# Felderblock6-a-2.net
KiCad netlist of a schematic drawn in EAGLE
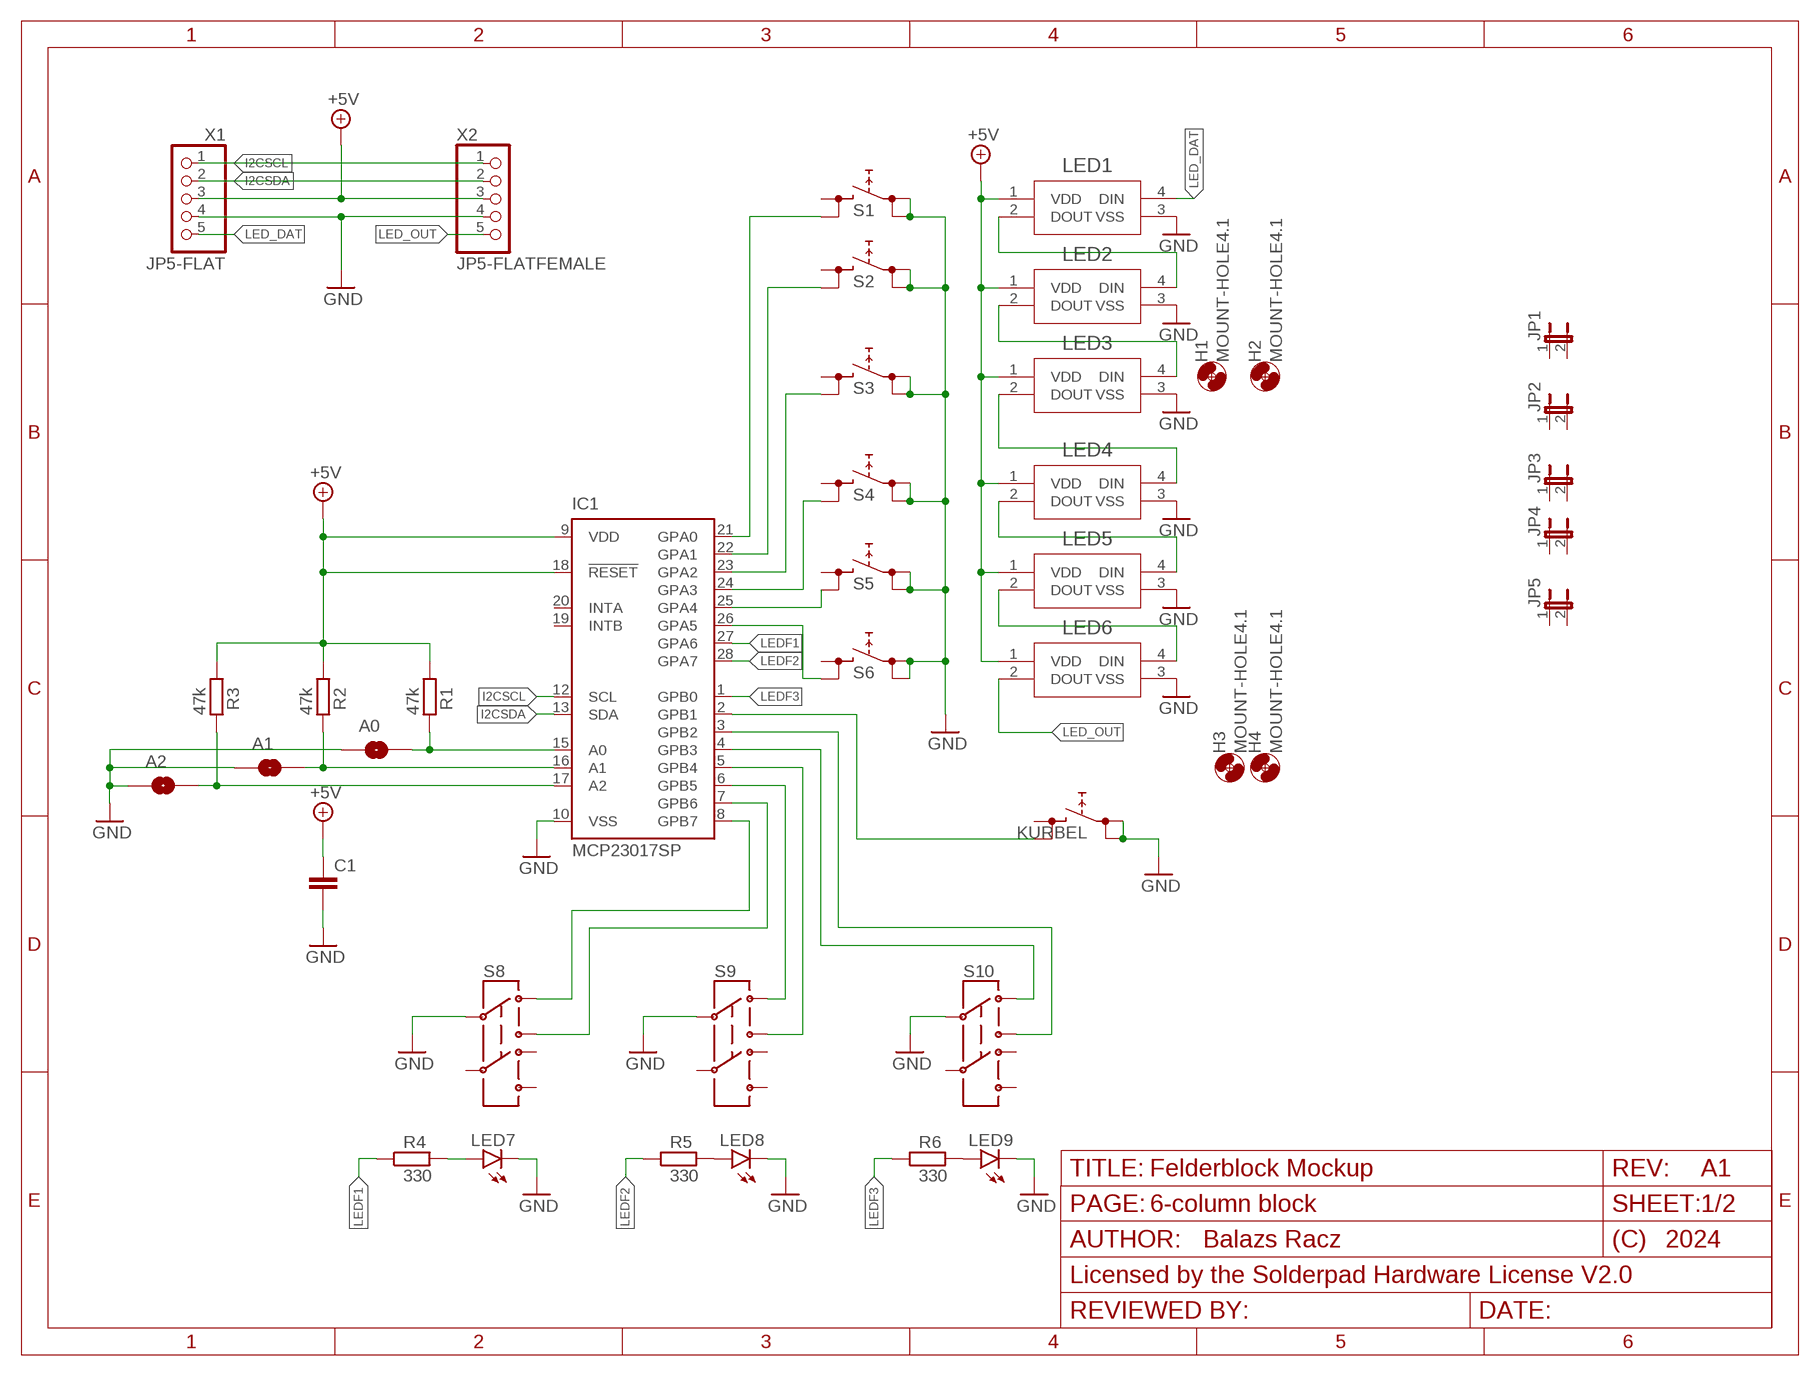
[diagram p0: schematic, sheet 1]

(export (version "E")
  (design (tool "Eeschema 10.0.6"))
  (components
    (comp (ref "A0")
      (value "SJRND2")
      (footprint "eagle-import:SJ_RND2")
      (libsource (lib "eagle-import") (part "SJRND2"))
    )
    (comp (ref "A1")
      (value "SJRND2")
      (footprint "eagle-import:SJ_RND2")
      (libsource (lib "eagle-import") (part "SJRND2"))
    )
    (comp (ref "A2")
      (value "SJRND2")
      (footprint "eagle-import:SJ_RND2")
      (libsource (lib "eagle-import") (part "SJRND2"))
    )
    (comp (ref "C1")
      (value "C-EUC0805")
      (footprint "eagle-import:C0805")
      (libsource (lib "eagle-import") (part "C-EUC0805"))
    )
    (comp (ref "H1")
      (value "MOUNT-HOLE4.1")
      (footprint "eagle-import:4,1")
      (libsource (lib "eagle-import") (part "MOUNT-HOLE4.1"))
    )
    (comp (ref "H2")
      (value "MOUNT-HOLE4.1")
      (footprint "eagle-import:4,1")
      (libsource (lib "eagle-import") (part "MOUNT-HOLE4.1"))
    )
    (comp (ref "H3")
      (value "MOUNT-HOLE4.1")
      (footprint "eagle-import:4,1")
      (libsource (lib "eagle-import") (part "MOUNT-HOLE4.1"))
    )
    (comp (ref "H4")
      (value "MOUNT-HOLE4.1")
      (footprint "eagle-import:4,1")
      (libsource (lib "eagle-import") (part "MOUNT-HOLE4.1"))
    )
    (comp (ref "IC1")
      (value "MCP23017SP")
      (footprint "eagle-import:DIL28-3")
      (fields (field (name "MF") "MICROCHIP") (field (name "MPN") "MCP23017-E/SP"))
      (libsource (lib "eagle-import") (part "MCP23017SP"))
    )
    (comp (ref "JP1")
      (value "FELD-BOARD-HOLDER")
      (footprint "eagle-import:FELD-BOARD-HOLDER")
      (libsource (lib "eagle-import") (part "FELD-BOARD-HOLDER"))
    )
    (comp (ref "JP2")
      (value "FELD-BOARD-HOLDER")
      (footprint "eagle-import:FELD-BOARD-HOLDER")
      (libsource (lib "eagle-import") (part "FELD-BOARD-HOLDER"))
    )
    (comp (ref "JP3")
      (value "FELD-BOARD-HOLDER")
      (footprint "eagle-import:FELD-BOARD-HOLDER")
      (libsource (lib "eagle-import") (part "FELD-BOARD-HOLDER"))
    )
    (comp (ref "JP4")
      (value "FELD-BOARD-HOLDER")
      (footprint "eagle-import:FELD-BOARD-HOLDER")
      (libsource (lib "eagle-import") (part "FELD-BOARD-HOLDER"))
    )
    (comp (ref "JP5")
      (value "FELD-BOARD-HOLDER")
      (footprint "eagle-import:FELD-BOARD-HOLDER")
      (libsource (lib "eagle-import") (part "FELD-BOARD-HOLDER"))
    )
    (comp (ref "KURBEL")
      (value "W1")
      (footprint "eagle-import:TACTSW-6X6")
      (libsource (lib "eagle-import") (part "TACTSW-6X6S"))
    )
    (comp (ref "LED1")
      (value "LED-2812BCOM-16347_SPK-M")
      (footprint "eagle-import:COM-16347_SPK-M")
      (fields
        (field (name "MANUFACTURER_PART_NUMBER") "COM-16347")
        (field (name "COPYRIGHT") "Copyright (C) 2024 Ultra Librarian. All rights reserved.")
      )
      (libsource (lib "eagle-import") (part "LED-2812BCOM-16347_SPK-M"))
    )
    (comp (ref "LED2")
      (value "LED-2812BCOM-16347_SPK-M")
      (footprint "eagle-import:COM-16347_SPK-M")
      (fields
        (field (name "MANUFACTURER_PART_NUMBER") "COM-16347")
        (field (name "COPYRIGHT") "Copyright (C) 2024 Ultra Librarian. All rights reserved.")
      )
      (libsource (lib "eagle-import") (part "LED-2812BCOM-16347_SPK-M"))
    )
    (comp (ref "LED3")
      (value "LED-2812BCOM-16347_SPK-M")
      (footprint "eagle-import:COM-16347_SPK-M")
      (fields
        (field (name "MANUFACTURER_PART_NUMBER") "COM-16347")
        (field (name "COPYRIGHT") "Copyright (C) 2024 Ultra Librarian. All rights reserved.")
      )
      (libsource (lib "eagle-import") (part "LED-2812BCOM-16347_SPK-M"))
    )
    (comp (ref "LED4")
      (value "LED-2812BCOM-16347_SPK-M")
      (footprint "eagle-import:COM-16347_SPK-M")
      (fields
        (field (name "MANUFACTURER_PART_NUMBER") "COM-16347")
        (field (name "COPYRIGHT") "Copyright (C) 2024 Ultra Librarian. All rights reserved.")
      )
      (libsource (lib "eagle-import") (part "LED-2812BCOM-16347_SPK-M"))
    )
    (comp (ref "LED5")
      (value "LED-2812BCOM-16347_SPK-M")
      (footprint "eagle-import:COM-16347_SPK-M")
      (fields
        (field (name "MANUFACTURER_PART_NUMBER") "COM-16347")
        (field (name "COPYRIGHT") "Copyright (C) 2024 Ultra Librarian. All rights reserved.")
      )
      (libsource (lib "eagle-import") (part "LED-2812BCOM-16347_SPK-M"))
    )
    (comp (ref "LED6")
      (value "LED-2812BCOM-16347_SPK-M")
      (footprint "eagle-import:COM-16347_SPK-M")
      (fields
        (field (name "MANUFACTURER_PART_NUMBER") "COM-16347")
        (field (name "COPYRIGHT") "Copyright (C) 2024 Ultra Librarian. All rights reserved.")
      )
      (libsource (lib "eagle-import") (part "LED-2812BCOM-16347_SPK-M"))
    )
    (comp (ref "LED7")
      (value "LEDCHIPLED_0805")
      (footprint "eagle-import:CHIPLED_0805")
      (libsource (lib "eagle-import") (part "LEDCHIPLED_0805"))
    )
    (comp (ref "LED8")
      (value "LEDCHIPLED_0805")
      (footprint "eagle-import:CHIPLED_0805")
      (libsource (lib "eagle-import") (part "LEDCHIPLED_0805"))
    )
    (comp (ref "LED9")
      (value "LEDCHIPLED_0805")
      (footprint "eagle-import:CHIPLED_0805")
      (libsource (lib "eagle-import") (part "LEDCHIPLED_0805"))
    )
    (comp (ref "R1")
      (value "47k")
      (footprint "eagle-import:R0805")
      (libsource (lib "eagle-import") (part "R-EU_R0805"))
    )
    (comp (ref "R2")
      (value "47k")
      (footprint "eagle-import:R0805")
      (libsource (lib "eagle-import") (part "R-EU_R0805"))
    )
    (comp (ref "R3")
      (value "47k")
      (footprint "eagle-import:R0805")
      (libsource (lib "eagle-import") (part "R-EU_R0805"))
    )
    (comp (ref "R4")
      (value "330")
      (footprint "eagle-import:R0805")
      (libsource (lib "eagle-import") (part "R-EU_R0805"))
    )
    (comp (ref "R5")
      (value "330")
      (footprint "eagle-import:R0805")
      (libsource (lib "eagle-import") (part "R-EU_R0805"))
    )
    (comp (ref "R6")
      (value "330")
      (footprint "eagle-import:R0805")
      (libsource (lib "eagle-import") (part "R-EU_R0805"))
    )
    (comp (ref "S1")
      (value "W1")
      (footprint "eagle-import:TACTSW-6X6")
      (libsource (lib "eagle-import") (part "TACTSW-6X6S"))
    )
    (comp (ref "S2")
      (value "W1")
      (footprint "eagle-import:TACTSW-6X6")
      (libsource (lib "eagle-import") (part "TACTSW-6X6S"))
    )
    (comp (ref "S3")
      (value "W1")
      (footprint "eagle-import:TACTSW-6X6")
      (libsource (lib "eagle-import") (part "TACTSW-6X6S"))
    )
    (comp (ref "S4")
      (value "W1")
      (footprint "eagle-import:TACTSW-6X6")
      (libsource (lib "eagle-import") (part "TACTSW-6X6S"))
    )
    (comp (ref "S5")
      (value "W1")
      (footprint "eagle-import:TACTSW-6X6")
      (libsource (lib "eagle-import") (part "TACTSW-6X6S"))
    )
    (comp (ref "S6")
      (value "W1")
      (footprint "eagle-import:TACTSW-6X6")
      (libsource (lib "eagle-import") (part "TACTSW-6X6S"))
    )
    (comp (ref "S8")
      (value "SWITCH-DPDT")
      (footprint "eagle-import:DP-T1")
      (libsource (lib "eagle-import") (part "SWITCH-DPDT"))
    )
    (comp (ref "S9")
      (value "SWITCH-DPDT")
      (footprint "eagle-import:DP-T1")
      (libsource (lib "eagle-import") (part "SWITCH-DPDT"))
    )
    (comp (ref "S10")
      (value "SWITCH-DPDT")
      (footprint "eagle-import:DP-T1")
      (libsource (lib "eagle-import") (part "SWITCH-DPDT"))
    )
    (comp (ref "X1")
      (value "JP5-FLAT")
      (footprint "eagle-import:JP5F")
      (libsource (lib "eagle-import") (part "JP5-FLAT"))
    )
    (comp (ref "X2")
      (value "JP5-FLATFEMALE")
      (footprint "eagle-import:JP5F-FEM")
      (libsource (lib "eagle-import") (part "JP5-FLATFEMALE"))
    )
  )
  (nets
    (net (code "1") (name "+5V") (class "Default")
      (node (ref "C1") (pin "1") (pinfunction "1_1") (pintype "passive"))
      (node (ref "IC1") (pin "18") (pinfunction "~{RESET}_18") (pintype "input"))
      (node (ref "IC1") (pin "9") (pinfunction "VDD_9") (pintype "power_in"))
      (node (ref "LED1") (pin "1") (pinfunction "VDD_1") (pintype "power_in"))
      (node (ref "LED2") (pin "1") (pinfunction "VDD_1") (pintype "power_in"))
      (node (ref "LED3") (pin "1") (pinfunction "VDD_1") (pintype "power_in"))
      (node (ref "LED4") (pin "1") (pinfunction "VDD_1") (pintype "power_in"))
      (node (ref "LED5") (pin "1") (pinfunction "VDD_1") (pintype "power_in"))
      (node (ref "LED6") (pin "1") (pinfunction "VDD_1") (pintype "power_in"))
      (node (ref "R1") (pin "1") (pinfunction "1_1") (pintype "passive"))
      (node (ref "R2") (pin "1") (pinfunction "1_1") (pintype "passive"))
      (node (ref "R3") (pin "1") (pinfunction "1_1") (pintype "passive"))
      (node (ref "X1") (pin "3") (pinfunction "3_3") (pintype "passive"))
      (node (ref "X2") (pin "3") (pinfunction "3_3") (pintype "passive"))
    )
    (net (code "2") (name "GND") (class "Default")
      (node (ref "A0") (pin "P$1") (pinfunction "1_P$1") (pintype "passive"))
      (node (ref "A1") (pin "P$1") (pinfunction "1_P$1") (pintype "passive"))
      (node (ref "A2") (pin "P$1") (pinfunction "1_P$1") (pintype "passive"))
      (node (ref "C1") (pin "2") (pinfunction "2_2") (pintype "passive"))
      (node (ref "IC1") (pin "10") (pinfunction "VSS_10") (pintype "power_in"))
      (node (ref "KURBEL") (pin "1") (pinfunction "1.1_1") (pintype "passive"))
      (node (ref "KURBEL") (pin "2") (pinfunction "1.2_2") (pintype "passive"))
      (node (ref "LED1") (pin "3") (pinfunction "VSS_3") (pintype "passive"))
      (node (ref "LED2") (pin "3") (pinfunction "VSS_3") (pintype "passive"))
      (node (ref "LED3") (pin "3") (pinfunction "VSS_3") (pintype "passive"))
      (node (ref "LED4") (pin "3") (pinfunction "VSS_3") (pintype "passive"))
      (node (ref "LED5") (pin "3") (pinfunction "VSS_3") (pintype "passive"))
      (node (ref "LED6") (pin "3") (pinfunction "VSS_3") (pintype "passive"))
      (node (ref "LED7") (pin "C") (pinfunction "C_C") (pintype "passive"))
      (node (ref "LED8") (pin "C") (pinfunction "C_C") (pintype "passive"))
      (node (ref "LED9") (pin "C") (pinfunction "C_C") (pintype "passive"))
      (node (ref "S1") (pin "1") (pinfunction "1.1_1") (pintype "passive"))
      (node (ref "S1") (pin "2") (pinfunction "1.2_2") (pintype "passive"))
      (node (ref "S10") (pin "2") (pinfunction "1C_2") (pintype "bidirectional"))
      (node (ref "S2") (pin "1") (pinfunction "1.1_1") (pintype "passive"))
      (node (ref "S2") (pin "2") (pinfunction "1.2_2") (pintype "passive"))
      (node (ref "S3") (pin "1") (pinfunction "1.1_1") (pintype "passive"))
      (node (ref "S3") (pin "2") (pinfunction "1.2_2") (pintype "passive"))
      (node (ref "S4") (pin "1") (pinfunction "1.1_1") (pintype "passive"))
      (node (ref "S4") (pin "2") (pinfunction "1.2_2") (pintype "passive"))
      (node (ref "S5") (pin "1") (pinfunction "1.1_1") (pintype "passive"))
      (node (ref "S5") (pin "2") (pinfunction "1.2_2") (pintype "passive"))
      (node (ref "S6") (pin "1") (pinfunction "1.1_1") (pintype "passive"))
      (node (ref "S6") (pin "2") (pinfunction "1.2_2") (pintype "passive"))
      (node (ref "S8") (pin "2") (pinfunction "1C_2") (pintype "bidirectional"))
      (node (ref "S9") (pin "2") (pinfunction "1C_2") (pintype "bidirectional"))
      (node (ref "X1") (pin "4") (pinfunction "4_4") (pintype "passive"))
      (node (ref "X2") (pin "4") (pinfunction "4_4") (pintype "passive"))
    )
    (net (code "3") (name "I2CSCL") (class "Default")
      (node (ref "IC1") (pin "12") (pinfunction "SCL_12") (pintype "input"))
      (node (ref "X1") (pin "1") (pinfunction "1_1") (pintype "passive"))
      (node (ref "X2") (pin "1") (pinfunction "1_1") (pintype "passive"))
    )
    (net (code "4") (name "I2CSDA") (class "Default")
      (node (ref "IC1") (pin "13") (pinfunction "SDA_13") (pintype "bidirectional"))
      (node (ref "X1") (pin "2") (pinfunction "2_2") (pintype "passive"))
      (node (ref "X2") (pin "2") (pinfunction "2_2") (pintype "passive"))
    )
    (net (code "5") (name "LEDF1") (class "Default")
      (node (ref "IC1") (pin "27") (pinfunction "GPA6_27") (pintype "bidirectional"))
      (node (ref "R4") (pin "1") (pinfunction "1_1") (pintype "passive"))
    )
    (net (code "6") (name "LEDF2") (class "Default")
      (node (ref "IC1") (pin "28") (pinfunction "GPA7_28") (pintype "bidirectional"))
      (node (ref "R5") (pin "1") (pinfunction "1_1") (pintype "passive"))
    )
    (net (code "7") (name "LEDF3") (class "Default")
      (node (ref "IC1") (pin "1") (pinfunction "GPB0_1") (pintype "bidirectional"))
      (node (ref "R6") (pin "1") (pinfunction "1_1") (pintype "passive"))
    )
    (net (code "8") (name "LED_DAT") (class "Default")
      (node (ref "LED1") (pin "4") (pinfunction "DIN_4") (pintype "input"))
      (node (ref "X1") (pin "5") (pinfunction "5_5") (pintype "passive"))
    )
    (net (code "9") (name "LED_OUT") (class "Default")
      (node (ref "LED6") (pin "2") (pinfunction "DOUT_2") (pintype "output"))
      (node (ref "X2") (pin "5") (pinfunction "5_5") (pintype "passive"))
    )
    (net (code "10") (name "Net-(A0-2)") (class "Default")
      (node (ref "A0") (pin "P$2") (pinfunction "2_P$2") (pintype "passive"))
      (node (ref "IC1") (pin "15") (pinfunction "A0_15") (pintype "input"))
      (node (ref "R1") (pin "2") (pinfunction "2_2") (pintype "passive"))
    )
    (net (code "11") (name "Net-(A1-2)") (class "Default")
      (node (ref "A1") (pin "P$2") (pinfunction "2_P$2") (pintype "passive"))
      (node (ref "IC1") (pin "16") (pinfunction "A1_16") (pintype "input"))
      (node (ref "R2") (pin "2") (pinfunction "2_2") (pintype "passive"))
    )
    (net (code "12") (name "Net-(A2-2)") (class "Default")
      (node (ref "A2") (pin "P$2") (pinfunction "2_P$2") (pintype "passive"))
      (node (ref "IC1") (pin "17") (pinfunction "A2_17") (pintype "input"))
      (node (ref "R3") (pin "2") (pinfunction "2_2") (pintype "passive"))
    )
    (net (code "13") (name "Net-(IC1-GPA0)") (class "Default")
      (node (ref "IC1") (pin "21") (pinfunction "GPA0_21") (pintype "bidirectional"))
      (node (ref "S1") (pin "4") (pinfunction "2.2_4") (pintype "passive"))
    )
    (net (code "14") (name "Net-(IC1-GPA1)") (class "Default")
      (node (ref "IC1") (pin "22") (pinfunction "GPA1_22") (pintype "bidirectional"))
      (node (ref "S2") (pin "4") (pinfunction "2.2_4") (pintype "passive"))
    )
    (net (code "15") (name "Net-(IC1-GPA2)") (class "Default")
      (node (ref "IC1") (pin "23") (pinfunction "GPA2_23") (pintype "bidirectional"))
      (node (ref "S3") (pin "4") (pinfunction "2.2_4") (pintype "passive"))
    )
    (net (code "16") (name "Net-(IC1-GPA3)") (class "Default")
      (node (ref "IC1") (pin "24") (pinfunction "GPA3_24") (pintype "bidirectional"))
      (node (ref "S4") (pin "4") (pinfunction "2.2_4") (pintype "passive"))
    )
    (net (code "17") (name "Net-(IC1-GPA4)") (class "Default")
      (node (ref "IC1") (pin "25") (pinfunction "GPA4_25") (pintype "bidirectional"))
      (node (ref "S5") (pin "4") (pinfunction "2.2_4") (pintype "passive"))
    )
    (net (code "18") (name "Net-(IC1-GPA5)") (class "Default")
      (node (ref "IC1") (pin "26") (pinfunction "GPA5_26") (pintype "bidirectional"))
      (node (ref "S6") (pin "4") (pinfunction "2.2_4") (pintype "passive"))
    )
    (net (code "19") (name "Net-(IC1-GPB1)") (class "Default")
      (node (ref "IC1") (pin "2") (pinfunction "GPB1_2") (pintype "bidirectional"))
      (node (ref "KURBEL") (pin "4") (pinfunction "2.2_4") (pintype "passive"))
    )
    (net (code "20") (name "Net-(IC1-GPB2)") (class "Default")
      (node (ref "IC1") (pin "3") (pinfunction "GPB2_3") (pintype "bidirectional"))
      (node (ref "S10") (pin "3") (pinfunction "1B_3") (pintype "bidirectional"))
    )
    (net (code "21") (name "Net-(IC1-GPB3)") (class "Default")
      (node (ref "IC1") (pin "4") (pinfunction "GPB3_4") (pintype "bidirectional"))
      (node (ref "S10") (pin "1") (pinfunction "1A_1") (pintype "bidirectional"))
    )
    (net (code "22") (name "Net-(IC1-GPB4)") (class "Default")
      (node (ref "IC1") (pin "5") (pinfunction "GPB4_5") (pintype "bidirectional"))
      (node (ref "S9") (pin "3") (pinfunction "1B_3") (pintype "bidirectional"))
    )
    (net (code "23") (name "Net-(IC1-GPB5)") (class "Default")
      (node (ref "IC1") (pin "6") (pinfunction "GPB5_6") (pintype "bidirectional"))
      (node (ref "S9") (pin "1") (pinfunction "1A_1") (pintype "bidirectional"))
    )
    (net (code "24") (name "Net-(IC1-GPB6)") (class "Default")
      (node (ref "IC1") (pin "7") (pinfunction "GPB6_7") (pintype "bidirectional"))
      (node (ref "S8") (pin "3") (pinfunction "1B_3") (pintype "bidirectional"))
    )
    (net (code "25") (name "Net-(IC1-GPB7)") (class "Default")
      (node (ref "IC1") (pin "8") (pinfunction "GPB7_8") (pintype "bidirectional"))
      (node (ref "S8") (pin "1") (pinfunction "1A_1") (pintype "bidirectional"))
    )
    (net (code "26") (name "Net-(LED1-DOUT)") (class "Default")
      (node (ref "LED1") (pin "2") (pinfunction "DOUT_2") (pintype "output"))
      (node (ref "LED2") (pin "4") (pinfunction "DIN_4") (pintype "input"))
    )
    (net (code "27") (name "Net-(LED2-DOUT)") (class "Default")
      (node (ref "LED2") (pin "2") (pinfunction "DOUT_2") (pintype "output"))
      (node (ref "LED3") (pin "4") (pinfunction "DIN_4") (pintype "input"))
    )
    (net (code "28") (name "Net-(LED3-DOUT)") (class "Default")
      (node (ref "LED3") (pin "2") (pinfunction "DOUT_2") (pintype "output"))
      (node (ref "LED4") (pin "4") (pinfunction "DIN_4") (pintype "input"))
    )
    (net (code "29") (name "Net-(LED4-DOUT)") (class "Default")
      (node (ref "LED4") (pin "2") (pinfunction "DOUT_2") (pintype "output"))
      (node (ref "LED5") (pin "4") (pinfunction "DIN_4") (pintype "input"))
    )
    (net (code "30") (name "Net-(LED5-DOUT)") (class "Default")
      (node (ref "LED5") (pin "2") (pinfunction "DOUT_2") (pintype "output"))
      (node (ref "LED6") (pin "4") (pinfunction "DIN_4") (pintype "input"))
    )
    (net (code "31") (name "Net-(LED7-PadA)") (class "Default")
      (node (ref "LED7") (pin "A") (pinfunction "A_A") (pintype "passive"))
      (node (ref "R4") (pin "2") (pinfunction "2_2") (pintype "passive"))
    )
    (net (code "32") (name "Net-(LED8-PadA)") (class "Default")
      (node (ref "LED8") (pin "A") (pinfunction "A_A") (pintype "passive"))
      (node (ref "R5") (pin "2") (pinfunction "2_2") (pintype "passive"))
    )
    (net (code "33") (name "Net-(LED9-PadA)") (class "Default")
      (node (ref "LED9") (pin "A") (pinfunction "A_A") (pintype "passive"))
      (node (ref "R6") (pin "2") (pinfunction "2_2") (pintype "passive"))
    )
    (net (code "34") (name "unconnected-(IC1-INTA-Pad20)") (class "Default")
      (node (ref "IC1") (pin "20") (pinfunction "INTA_20") (pintype "output"))
    )
    (net (code "35") (name "unconnected-(IC1-INTB-Pad19)") (class "Default")
      (node (ref "IC1") (pin "19") (pinfunction "INTB_19") (pintype "output"))
    )
    (net (code "36") (name "unconnected-(JP1-Pad1)") (class "Default")
      (node (ref "JP1") (pin "1") (pinfunction "1_1") (pintype "passive"))
    )
    (net (code "37") (name "unconnected-(JP1-Pad2)") (class "Default")
      (node (ref "JP1") (pin "2") (pinfunction "2_2") (pintype "passive"))
    )
    (net (code "38") (name "unconnected-(JP2-Pad1)") (class "Default")
      (node (ref "JP2") (pin "1") (pinfunction "1_1") (pintype "passive"))
    )
    (net (code "39") (name "unconnected-(JP2-Pad2)") (class "Default")
      (node (ref "JP2") (pin "2") (pinfunction "2_2") (pintype "passive"))
    )
    (net (code "40") (name "unconnected-(JP3-Pad1)") (class "Default")
      (node (ref "JP3") (pin "1") (pinfunction "1_1") (pintype "passive"))
    )
    (net (code "41") (name "unconnected-(JP3-Pad2)") (class "Default")
      (node (ref "JP3") (pin "2") (pinfunction "2_2") (pintype "passive"))
    )
    (net (code "42") (name "unconnected-(JP4-Pad1)") (class "Default")
      (node (ref "JP4") (pin "1") (pinfunction "1_1") (pintype "passive"))
    )
    (net (code "43") (name "unconnected-(JP4-Pad2)") (class "Default")
      (node (ref "JP4") (pin "2") (pinfunction "2_2") (pintype "passive"))
    )
    (net (code "44") (name "unconnected-(JP5-Pad1)") (class "Default")
      (node (ref "JP5") (pin "1") (pinfunction "1_1") (pintype "passive"))
    )
    (net (code "45") (name "unconnected-(JP5-Pad2)") (class "Default")
      (node (ref "JP5") (pin "2") (pinfunction "2_2") (pintype "passive"))
    )
    (net (code "46") (name "unconnected-(KURBEL-2.1-Pad3)") (class "Default")
      (node (ref "KURBEL") (pin "3") (pinfunction "2.1_3") (pintype "passive"))
    )
    (net (code "47") (name "unconnected-(S1-2.1-Pad3)") (class "Default")
      (node (ref "S1") (pin "3") (pinfunction "2.1_3") (pintype "passive"))
    )
    (net (code "48") (name "unconnected-(S2-2.1-Pad3)") (class "Default")
      (node (ref "S2") (pin "3") (pinfunction "2.1_3") (pintype "passive"))
    )
    (net (code "49") (name "unconnected-(S3-2.1-Pad3)") (class "Default")
      (node (ref "S3") (pin "3") (pinfunction "2.1_3") (pintype "passive"))
    )
    (net (code "50") (name "unconnected-(S4-2.1-Pad3)") (class "Default")
      (node (ref "S4") (pin "3") (pinfunction "2.1_3") (pintype "passive"))
    )
    (net (code "51") (name "unconnected-(S5-2.1-Pad3)") (class "Default")
      (node (ref "S5") (pin "3") (pinfunction "2.1_3") (pintype "passive"))
    )
    (net (code "52") (name "unconnected-(S6-2.1-Pad3)") (class "Default")
      (node (ref "S6") (pin "3") (pinfunction "2.1_3") (pintype "passive"))
    )
    (net (code "53") (name "unconnected-(S8-2A-Pad4)") (class "Default")
      (node (ref "S8") (pin "4") (pinfunction "2A_4") (pintype "bidirectional"))
    )
    (net (code "54") (name "unconnected-(S8-2B-Pad6)") (class "Default")
      (node (ref "S8") (pin "6") (pinfunction "2B_6") (pintype "bidirectional"))
    )
    (net (code "55") (name "unconnected-(S8-2C-Pad5)") (class "Default")
      (node (ref "S8") (pin "5") (pinfunction "2C_5") (pintype "bidirectional"))
    )
    (net (code "56") (name "unconnected-(S9-2A-Pad4)") (class "Default")
      (node (ref "S9") (pin "4") (pinfunction "2A_4") (pintype "bidirectional"))
    )
    (net (code "57") (name "unconnected-(S9-2B-Pad6)") (class "Default")
      (node (ref "S9") (pin "6") (pinfunction "2B_6") (pintype "bidirectional"))
    )
    (net (code "58") (name "unconnected-(S9-2C-Pad5)") (class "Default")
      (node (ref "S9") (pin "5") (pinfunction "2C_5") (pintype "bidirectional"))
    )
    (net (code "59") (name "unconnected-(S10-2A-Pad4)") (class "Default")
      (node (ref "S10") (pin "4") (pinfunction "2A_4") (pintype "bidirectional"))
    )
    (net (code "60") (name "unconnected-(S10-2B-Pad6)") (class "Default")
      (node (ref "S10") (pin "6") (pinfunction "2B_6") (pintype "bidirectional"))
    )
    (net (code "61") (name "unconnected-(S10-2C-Pad5)") (class "Default")
      (node (ref "S10") (pin "5") (pinfunction "2C_5") (pintype "bidirectional"))
    )
  )
)
